# Sheet1.net
KiCad netlist of a schematic drawn in Altium Designer
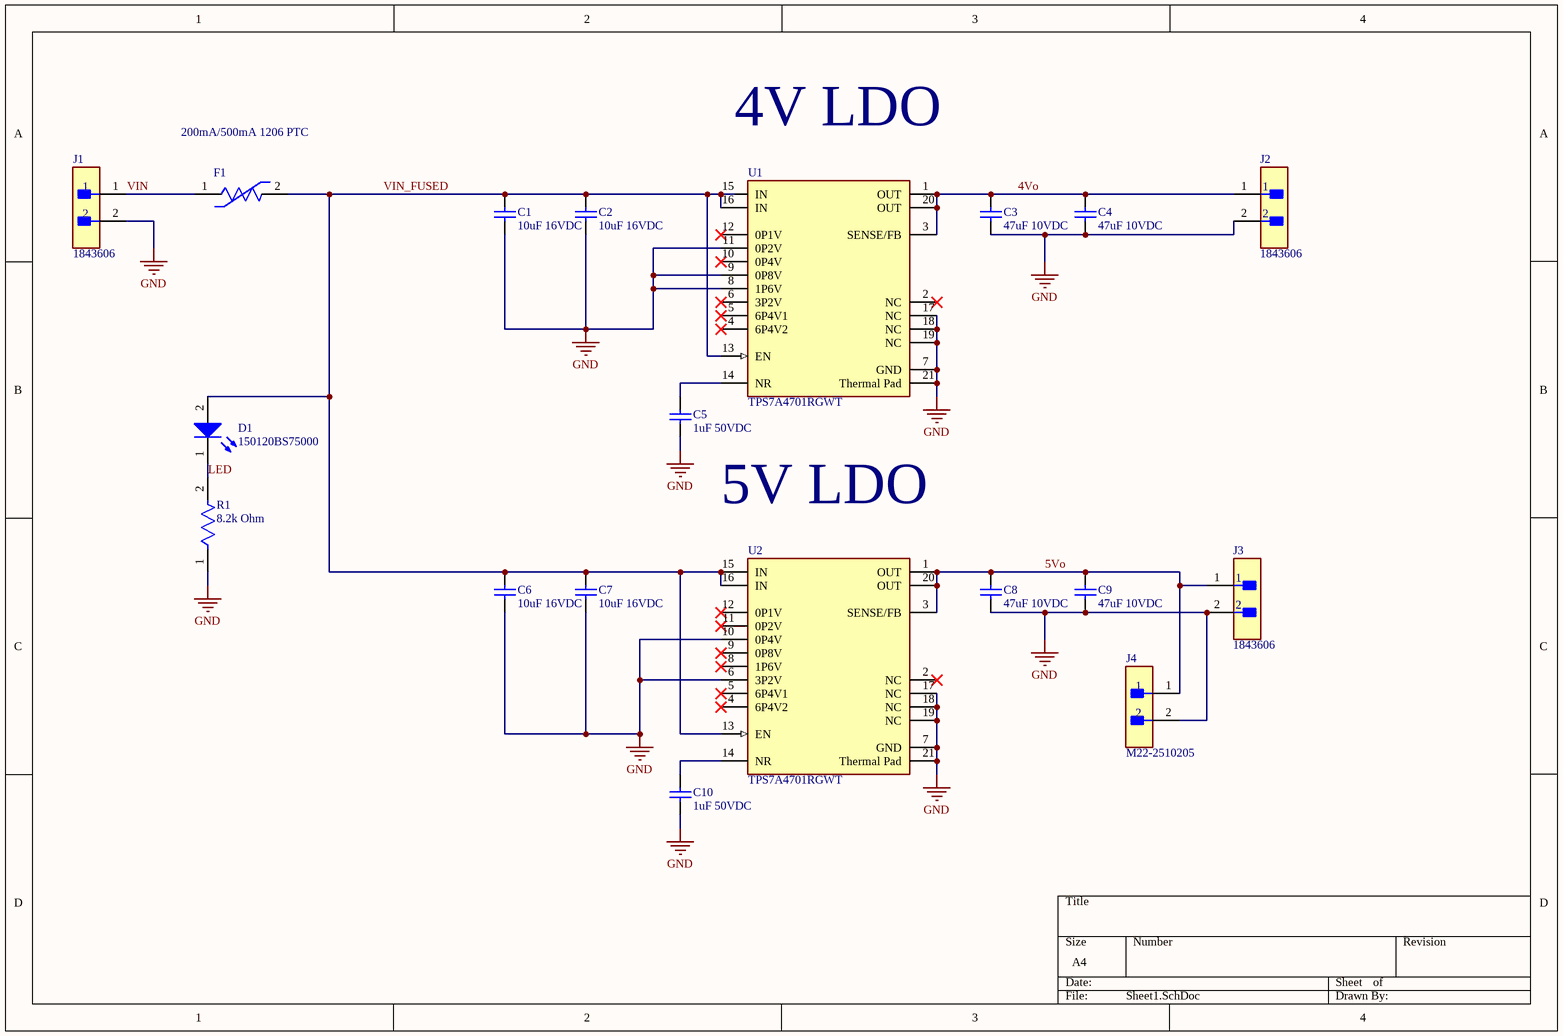
[diagram p0: Sheet1.SchDoc]

(export (version "E")
  (design (tool "Eeschema 10.0.6"))
  (components
    (comp (ref "C1")
      (value "10uF 16VDC")
      (footprint "CAPC1206(3216)170_M")
      (description "CL31B106KOHNNNE10uF 16VDC")
      (fields (field (name "TOLERANCE") "Â±2%"))
      (libsource (lib "Altium Content Vault") (part "CAP"))
    )
    (comp (ref "C2")
      (value "10uF 16VDC")
      (footprint "CAPC1206(3216)170_M")
      (description "CL31B106KOHNNNE10uF 16VDC")
      (fields (field (name "TOLERANCE") "Â±2%"))
      (libsource (lib "Altium Content Vault") (part "CAP"))
    )
    (comp (ref "C3")
      (value "47uF 10VDC")
      (footprint "CAPC1206(3216)170_M")
      (description "CL31A476MPHNNN 47uF 10V")
      (fields (field (name "TOLERANCE") "Â±2%"))
      (libsource (lib "Altium Content Vault") (part "CAP"))
    )
    (comp (ref "C4")
      (value "47uF 10VDC")
      (footprint "CAPC1206(3216)170_M")
      (description "CL31A476MPHNNN 47uF 10V")
      (fields (field (name "TOLERANCE") "Â±2%"))
      (libsource (lib "Altium Content Vault") (part "CAP"))
    )
    (comp (ref "C5")
      (value "1uF 50VDC")
      (footprint "CAPC1206(3216)170_M")
      (description "CC1206KKX7R7BB1051uF 50VDC")
      (fields (field (name "TOLERANCE") "Â±2%"))
      (libsource (lib "Altium Content Vault") (part "CAP"))
    )
    (comp (ref "C6")
      (value "10uF 16VDC")
      (footprint "CAPC1206(3216)170_M")
      (description "CL31B106KOHNNNE10uF 16VDC")
      (fields (field (name "TOLERANCE") "Â±2%"))
      (libsource (lib "Altium Content Vault") (part "CAP"))
    )
    (comp (ref "C7")
      (value "10uF 16VDC")
      (footprint "CAPC1206(3216)170_M")
      (description "CL31B106KOHNNNE10uF 16VDC")
      (fields (field (name "TOLERANCE") "Â±2%"))
      (libsource (lib "Altium Content Vault") (part "CAP"))
    )
    (comp (ref "C8")
      (value "47uF 10VDC")
      (footprint "CAPC1206(3216)170_M")
      (description "CL31A476MPHNNN 47uF 10V")
      (fields (field (name "TOLERANCE") "Â±2%"))
      (libsource (lib "Altium Content Vault") (part "CAP"))
    )
    (comp (ref "C9")
      (value "47uF 10VDC")
      (footprint "CAPC1206(3216)170_M")
      (description "CL31A476MPHNNN 47uF 10V")
      (fields (field (name "TOLERANCE") "Â±2%"))
      (libsource (lib "Altium Content Vault") (part "CAP"))
    )
    (comp (ref "C10")
      (value "1uF 50VDC")
      (footprint "CAPC1206(3216)170_M")
      (description "CC1206KKX7R7BB1051uF 50VDC")
      (fields (field (name "TOLERANCE") "Â±2%"))
      (libsource (lib "Altium Content Vault") (part "CAP"))
    )
    (comp (ref "D1")
      (value "150120BS75000")
      (footprint "WL-SMCW_1206_150120xx75000")
      (description "WL-SMCW SMT Mono-Color Chip LED Waterclear")
      (libsource (lib "Altium Content Vault") (part "LED_Blue_2A-1K"))
    )
    (comp (ref "F1")
      (value "200mA/500mA 1206 PTC")
      (footprint "FP-nanoSMD400LR-IPC_A")
      (description "PTC RESET FUSE 6V 4A 1206")
      (libsource (lib "Altium Content Vault") (part "fdf083d5f6389a9a1c4e51137f46658"))
    )
    (comp (ref "J1")
      (value "1843606")
      (footprint "FP-1843606-MFG")
      (description "1843606 Phoenix Contact 1843606 MCV 1, 5/ 2-G-3, 5 2 Way Terminal Block Header 8A 3.5mm")
      (fields (field (name "VOLTAGE") "300V"))
      (libsource (lib "Altium Content Vault") (part "3bc925449376181038e59eaffc5286c"))
    )
    (comp (ref "J2")
      (value "1843606")
      (footprint "FP-1843606-MFG")
      (description "1843606 Phoenix Contact 1843606 MCV 1, 5/ 2-G-3, 5 2 Way Terminal Block Header 8A 3.5mm")
      (fields (field (name "VOLTAGE") "300V"))
      (libsource (lib "") (part "3bc925449376181038e59eaffc5286c_1"))
    )
    (comp (ref "J3")
      (value "1843606")
      (footprint "FP-1843606-MFG")
      (description "1843606 Phoenix Contact 1843606 MCV 1, 5/ 2-G-3, 5 2 Way Terminal Block Header 8A 3.5mm")
      (fields (field (name "VOLTAGE") "300V"))
      (libsource (lib "") (part "3bc925449376181038e59eaffc5286c_1"))
    )
    (comp (ref "J4")
      (value "M22-2510205")
      (footprint "FP-M22-2510205-MFG")
      (description "CONN HEADER VERT 2POS 2MM")
      (fields
        (field (name "MANUFACTURER") "Harwin")
        (field (name "OCTOPART") "https://octopart.com/m22-2510205-harwin-2538221")
      )
      (libsource (lib "Altium Content Vault") (part "3bc925449376181038e59eaffc5286c"))
    )
    (comp (ref "R1")
      (value "8.2k Ohm")
      (footprint "FP-RMCF1206-IPC_A")
      (description "8.2k Ohm 1206")
      (fields (field (name "TOLERANCE") "1%"))
      (libsource (lib "Altium Content Vault") (part "1029c3af85768c4190bb7ad29bc67b5"))
    )
    (comp (ref "U1")
      (value "TPS7A4701RGWT")
      (footprint "FP-RGW0020A-MFG")
      (description "IC REG LINEAR POS ADJ 1A 20VQFN")
      (fields
        (field (name "OCTOPART") "https://octopart.com/tps7a4701rgwt-texas+instruments-30261754")
        (field (name "MANUFACTURER") "Texas Instruments")
      )
      (libsource (lib "Altium Content Vault") (part "75ed804cb6a60024ba8af184cb58ac1"))
    )
    (comp (ref "U2")
      (value "TPS7A4701RGWT")
      (footprint "FP-RGW0020A-MFG")
      (description "IC REG LINEAR POS ADJ 1A 20VQFN")
      (fields
        (field (name "OCTOPART") "https://octopart.com/tps7a4701rgwt-texas+instruments-30261754")
        (field (name "MANUFACTURER") "Texas Instruments")
      )
      (libsource (lib "Altium Content Vault") (part "75ed804cb6a60024ba8af184cb58ac1"))
    )
  )
  (nets
    (net (code "1") (name "/4Vo") (class "Default")
      (node (ref "C3") (pin "2") (pinfunction "2_2") (pintype "passive"))
      (node (ref "C4") (pin "2") (pinfunction "2_2") (pintype "passive"))
      (node (ref "J2") (pin "1") (pinfunction "1_1") (pintype "passive"))
      (node (ref "U1") (pin "1") (pinfunction "OUT_1") (pintype "passive"))
      (node (ref "U1") (pin "20") (pinfunction "OUT_20") (pintype "passive"))
      (node (ref "U1") (pin "3") (pinfunction "SENSE/FB_3") (pintype "passive"))
    )
    (net (code "2") (name "/5Vo") (class "Default")
      (node (ref "C8") (pin "2") (pinfunction "2_2") (pintype "passive"))
      (node (ref "C9") (pin "2") (pinfunction "2_2") (pintype "passive"))
      (node (ref "J3") (pin "1") (pinfunction "1_1") (pintype "passive"))
      (node (ref "J4") (pin "1") (pinfunction "1_1") (pintype "passive"))
      (node (ref "U2") (pin "1") (pinfunction "OUT_1") (pintype "passive"))
      (node (ref "U2") (pin "20") (pinfunction "OUT_20") (pintype "passive"))
      (node (ref "U2") (pin "3") (pinfunction "SENSE/FB_3") (pintype "passive"))
    )
    (net (code "3") (name "/LED") (class "Default")
      (node (ref "D1") (pin "1") (pinfunction "K_1") (pintype "passive"))
      (node (ref "R1") (pin "2") (pinfunction "2_2") (pintype "passive"))
    )
    (net (code "4") (name "/VIN") (class "Default")
      (node (ref "F1") (pin "1") (pinfunction "1_1") (pintype "passive"))
      (node (ref "J1") (pin "1") (pinfunction "1_1") (pintype "passive"))
    )
    (net (code "5") (name "/VIN_FUSED") (class "Default")
      (node (ref "C1") (pin "2") (pinfunction "2_2") (pintype "passive"))
      (node (ref "C2") (pin "2") (pinfunction "2_2") (pintype "passive"))
      (node (ref "C6") (pin "2") (pinfunction "2_2") (pintype "passive"))
      (node (ref "C7") (pin "2") (pinfunction "2_2") (pintype "passive"))
      (node (ref "D1") (pin "2") (pinfunction "A_2") (pintype "passive"))
      (node (ref "F1") (pin "2") (pinfunction "2_2") (pintype "passive"))
      (node (ref "U1") (pin "13") (pinfunction "EN_13") (pintype "input"))
      (node (ref "U1") (pin "15") (pinfunction "IN_15") (pintype "power_in"))
      (node (ref "U1") (pin "16") (pinfunction "IN_16") (pintype "power_in"))
      (node (ref "U2") (pin "13") (pinfunction "EN_13") (pintype "input"))
      (node (ref "U2") (pin "15") (pinfunction "IN_15") (pintype "power_in"))
      (node (ref "U2") (pin "16") (pinfunction "IN_16") (pintype "power_in"))
    )
    (net (code "6") (name "GND") (class "Default")
      (node (ref "C1") (pin "1") (pinfunction "1_1") (pintype "passive"))
      (node (ref "C10") (pin "1") (pinfunction "1_1") (pintype "passive"))
      (node (ref "C2") (pin "1") (pinfunction "1_1") (pintype "passive"))
      (node (ref "C3") (pin "1") (pinfunction "1_1") (pintype "passive"))
      (node (ref "C4") (pin "1") (pinfunction "1_1") (pintype "passive"))
      (node (ref "C5") (pin "1") (pinfunction "1_1") (pintype "passive"))
      (node (ref "C6") (pin "1") (pinfunction "1_1") (pintype "passive"))
      (node (ref "C7") (pin "1") (pinfunction "1_1") (pintype "passive"))
      (node (ref "C8") (pin "1") (pinfunction "1_1") (pintype "passive"))
      (node (ref "C9") (pin "1") (pinfunction "1_1") (pintype "passive"))
      (node (ref "J1") (pin "2") (pinfunction "2_2") (pintype "passive"))
      (node (ref "J2") (pin "2") (pinfunction "2_2") (pintype "passive"))
      (node (ref "J3") (pin "2") (pinfunction "2_2") (pintype "passive"))
      (node (ref "J4") (pin "2") (pinfunction "2_2") (pintype "passive"))
      (node (ref "R1") (pin "1") (pinfunction "1_1") (pintype "passive"))
      (node (ref "U1") (pin "11") (pinfunction "0P2V_11") (pintype "passive"))
      (node (ref "U1") (pin "17") (pinfunction "NC_17") (pintype "passive"))
      (node (ref "U1") (pin "18") (pinfunction "NC_18") (pintype "passive"))
      (node (ref "U1") (pin "19") (pinfunction "NC_19") (pintype "passive"))
      (node (ref "U1") (pin "21") (pinfunction "Thermal_Pad_21") (pintype "power_in"))
      (node (ref "U1") (pin "7") (pinfunction "GND_7") (pintype "power_in"))
      (node (ref "U1") (pin "8") (pinfunction "1P6V_8") (pintype "passive"))
      (node (ref "U1") (pin "9") (pinfunction "0P8V_9") (pintype "passive"))
      (node (ref "U2") (pin "10") (pinfunction "0P4V_10") (pintype "passive"))
      (node (ref "U2") (pin "17") (pinfunction "NC_17") (pintype "passive"))
      (node (ref "U2") (pin "18") (pinfunction "NC_18") (pintype "passive"))
      (node (ref "U2") (pin "19") (pinfunction "NC_19") (pintype "passive"))
      (node (ref "U2") (pin "21") (pinfunction "Thermal_Pad_21") (pintype "power_in"))
      (node (ref "U2") (pin "6") (pinfunction "3P2V_6") (pintype "passive"))
      (node (ref "U2") (pin "7") (pinfunction "GND_7") (pintype "power_in"))
    )
    (net (code "7") (name "Net-(U1-NR)") (class "Default")
      (node (ref "C5") (pin "2") (pinfunction "2_2") (pintype "passive"))
      (node (ref "U1") (pin "14") (pinfunction "NR_14") (pintype "passive"))
    )
    (net (code "8") (name "Net-(U2-NR)") (class "Default")
      (node (ref "C10") (pin "2") (pinfunction "2_2") (pintype "passive"))
      (node (ref "U2") (pin "14") (pinfunction "NR_14") (pintype "passive"))
    )
    (net (code "9") (name "unconnected-(U1-0P1V-Pad12)") (class "Default")
      (node (ref "U1") (pin "12") (pinfunction "0P1V_12") (pintype "passive+no_connect"))
    )
    (net (code "10") (name "unconnected-(U1-0P4V-Pad10)") (class "Default")
      (node (ref "U1") (pin "10") (pinfunction "0P4V_10") (pintype "passive+no_connect"))
    )
    (net (code "11") (name "unconnected-(U1-3P2V-Pad6)") (class "Default")
      (node (ref "U1") (pin "6") (pinfunction "3P2V_6") (pintype "passive+no_connect"))
    )
    (net (code "12") (name "unconnected-(U1-6P4V1-Pad5)") (class "Default")
      (node (ref "U1") (pin "5") (pinfunction "6P4V1_5") (pintype "passive+no_connect"))
    )
    (net (code "13") (name "unconnected-(U1-6P4V2-Pad4)") (class "Default")
      (node (ref "U1") (pin "4") (pinfunction "6P4V2_4") (pintype "passive+no_connect"))
    )
    (net (code "14") (name "unconnected-(U1-NC-Pad2)") (class "Default")
      (node (ref "U1") (pin "2") (pinfunction "NC_2") (pintype "passive+no_connect"))
    )
    (net (code "15") (name "unconnected-(U2-0P1V-Pad12)") (class "Default")
      (node (ref "U2") (pin "12") (pinfunction "0P1V_12") (pintype "passive+no_connect"))
    )
    (net (code "16") (name "unconnected-(U2-0P2V-Pad11)") (class "Default")
      (node (ref "U2") (pin "11") (pinfunction "0P2V_11") (pintype "passive+no_connect"))
    )
    (net (code "17") (name "unconnected-(U2-0P8V-Pad9)") (class "Default")
      (node (ref "U2") (pin "9") (pinfunction "0P8V_9") (pintype "passive+no_connect"))
    )
    (net (code "18") (name "unconnected-(U2-1P6V-Pad8)") (class "Default")
      (node (ref "U2") (pin "8") (pinfunction "1P6V_8") (pintype "passive+no_connect"))
    )
    (net (code "19") (name "unconnected-(U2-6P4V1-Pad5)") (class "Default")
      (node (ref "U2") (pin "5") (pinfunction "6P4V1_5") (pintype "passive+no_connect"))
    )
    (net (code "20") (name "unconnected-(U2-6P4V2-Pad4)") (class "Default")
      (node (ref "U2") (pin "4") (pinfunction "6P4V2_4") (pintype "passive+no_connect"))
    )
    (net (code "21") (name "unconnected-(U2-NC-Pad2)") (class "Default")
      (node (ref "U2") (pin "2") (pinfunction "NC_2") (pintype "passive+no_connect"))
    )
  )
)
